# Wireless.net
KiCad netlist of a schematic drawn in EasyEDA
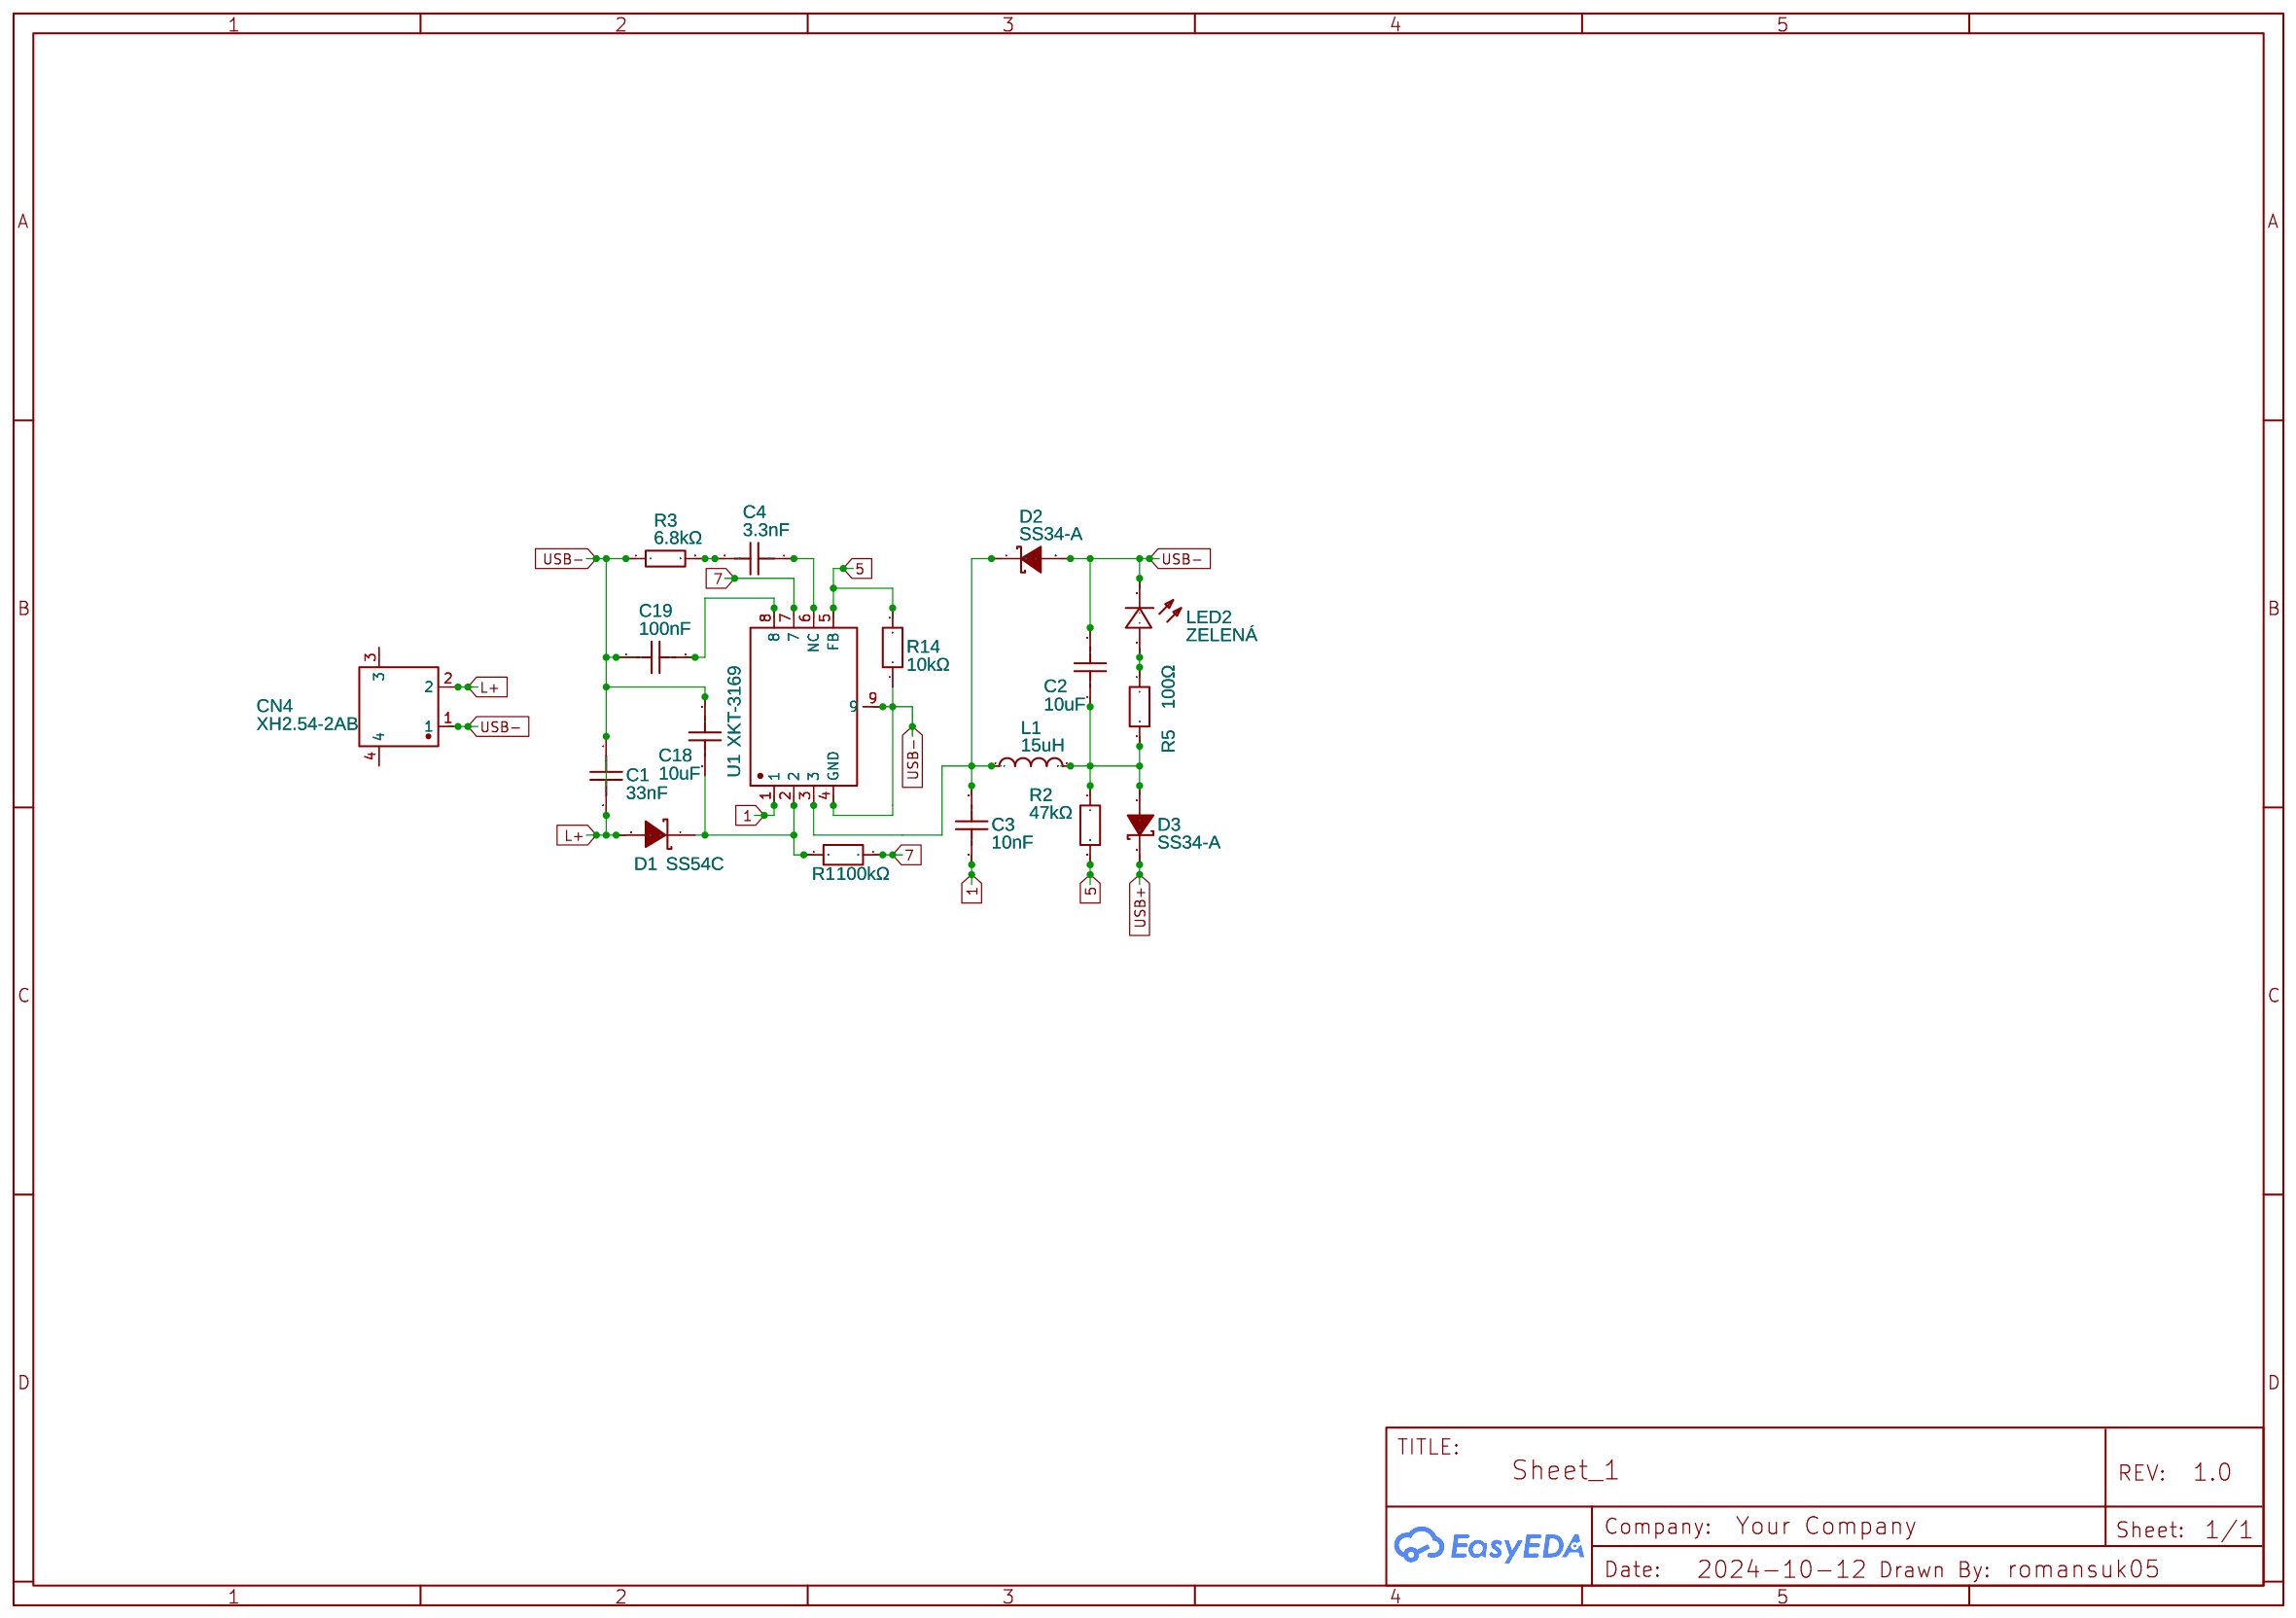
[diagram p0: schematic sheet]

(export (version "E")
  (design (tool "Eeschema 10.0.6"))
  (components
    (comp (ref "C1")
      (value "33nF")
      (fields
        (field (name "Manufacturer Part") "GRM31CR72E333KW03L")
        (field (name "Manufacturer") "muRata(村田)")
      )
      (libsource (lib "") (part "GRM31CR72E333KW03L"))
    )
    (comp (ref "C2")
      (value "10uF")
      (fields
        (field (name "Manufacturer Part") "TCC1206X7R106K250HT")
        (field (name "Manufacturer") "CCTC(三环)")
      )
      (libsource (lib "") (part "TCC1206X7R106K250HT"))
    )
    (comp (ref "C3")
      (value "10nF")
      (fields
        (field (name "Manufacturer Part") "CC1206JKNPOZBN103")
        (field (name "Manufacturer") "YAGEO(国巨)")
      )
      (libsource (lib "") (part "CC1206JKNPOZBN103"))
    )
    (comp (ref "C4")
      (value "3.3nF")
      (fields
        (field (name "Manufacturer Part") "TCC1206X7R332K501DT")
        (field (name "Manufacturer") "CCTC(三环)")
      )
      (libsource (lib "") (part "TCC1206X7R332K501DT"))
    )
    (comp (ref "C18")
      (value "10uF")
      (fields
        (field (name "Manufacturer Part") "TCC1206X7R106K250HT")
        (field (name "Manufacturer") "CCTC(三环)")
      )
      (libsource (lib "") (part "TCC1206X7R106K250HT"))
    )
    (comp (ref "C19")
      (value "100nF")
      (fields
        (field (name "Manufacturer Part") "C1206X104J1RECAUTO7210")
        (field (name "Manufacturer") "KEMET(基美)")
      )
      (libsource (lib "") (part "C1206X104J1RECAUTO7210"))
    )
    (comp (ref "CN4")
      (value "XH2.54-2AB")
      (fields (field (name "Manufacturer Part") "XH-2P立贴") (field (name "Manufacturer") "BOOMELE(博穆精密)"))
      (libsource (lib "") (part "XH2.54-2AB"))
    )
    (comp (ref "D1")
      (value "SS54C")
      (fields (field (name "Manufacturer Part") "SS54") (field (name "Manufacturer") "LGE(鲁光)"))
      (libsource (lib "") (part "SS54C"))
    )
    (comp (ref "D2")
      (value "SS34-A")
      (fields (field (name "Manufacturer") "FMS(美丽微)"))
      (libsource (lib "") (part "SS34-A"))
    )
    (comp (ref "D3")
      (value "SS34-A")
      (fields (field (name "Manufacturer") "FMS(美丽微)"))
      (libsource (lib "") (part "SS34-A_1"))
    )
    (comp (ref "L1")
      (value "15uH")
      (fields
        (field (name "Manufacturer Part") "MSCD43-150KT")
        (field (name "Manufacturer") "MetalLions(美铼)")
      )
      (libsource (lib "") (part "MSCD43-150KT"))
    )
    (comp (ref "LED2")
      (value "ZELENÁ")
      (fields
        (field (name "Manufacturer Part") "E6C1206URAC1UDA")
        (field (name "Manufacturer") "ekinglux(亿晶源)")
      )
      (libsource (lib "") (part "E6C1206URAC1UDA"))
    )
    (comp (ref "R1")
      (value "100kΩ")
      (fields (field (name "Manufacturer Part") "PTFR1206B100KN9") (field (name "Manufacturer") "RESI(开步睿思)"))
      (libsource (lib "") (part "PTFR1206B100KN9"))
    )
    (comp (ref "R2")
      (value "47kΩ")
      (fields
        (field (name "Manufacturer Part") "CR1206J47KP05")
        (field (name "Manufacturer") "EVER OHMS(天二科技)")
      )
      (libsource (lib "") (part "CR1206J47KP05"))
    )
    (comp (ref "R3")
      (value "6.8kΩ")
      (fields (field (name "Manufacturer Part") "AC1206FR-076K8L") (field (name "Manufacturer") "YAGEO(国巨)"))
      (libsource (lib "") (part "AC1206FR-076K8L"))
    )
    (comp (ref "R5")
      (value "100Ω")
      (fields (field (name "Manufacturer Part") "SCR1206F100R") (field (name "Manufacturer") "VO(翔胜)"))
      (libsource (lib "") (part "SCR1206F100R"))
    )
    (comp (ref "R14")
      (value "10kΩ")
      (fields (field (name "Manufacturer Part") "SCR1206F10K") (field (name "Manufacturer") "VO(翔胜)"))
      (libsource (lib "") (part "SCR1206F10K"))
    )
    (comp (ref "U1")
      (value "XKT-3169")
      (fields (field (name "Manufacturer") "MAXIM"))
      (libsource (lib "") (part "XKT-3169"))
    )
  )
  (nets
    (net (code "1") (name "1") (class "Default")
      (node (ref "C3") (pin "1") (pinfunction "1_1") (pintype "unspecified"))
      (node (ref "U1") (pin "1") (pinfunction "1_1") (pintype "unspecified"))
    )
    (net (code "2") (name "5") (class "Default")
      (node (ref "R14") (pin "2") (pinfunction "2_2") (pintype "unspecified"))
      (node (ref "R2") (pin "2") (pinfunction "2_2") (pintype "unspecified"))
      (node (ref "U1") (pin "5") (pinfunction "FB_5") (pintype "unspecified"))
    )
    (net (code "3") (name "7") (class "Default")
      (node (ref "R1") (pin "2") (pinfunction "2_2") (pintype "unspecified"))
      (node (ref "U1") (pin "7") (pinfunction "7_7") (pintype "unspecified"))
    )
    (net (code "4") (name "L+") (class "Default")
      (node (ref "C1") (pin "2") (pinfunction "2_2") (pintype "unspecified"))
      (node (ref "CN4") (pin "2") (pinfunction "2_2") (pintype "unspecified"))
      (node (ref "D1") (pin "2") (pinfunction "A_2") (pintype "unspecified"))
    )
    (net (code "5") (name "Net-(C4-Pad2)") (class "Default")
      (node (ref "C4") (pin "2") (pinfunction "2_2") (pintype "unspecified"))
      (node (ref "R3") (pin "2") (pinfunction "2_2") (pintype "unspecified"))
    )
    (net (code "6") (name "Net-(C19-Pad2)") (class "Default")
      (node (ref "C19") (pin "2") (pinfunction "2_2") (pintype "unspecified"))
      (node (ref "U1") (pin "8") (pinfunction "8_8") (pintype "unspecified"))
    )
    (net (code "7") (name "Net-(D1-K)") (class "Default")
      (node (ref "C18") (pin "2") (pinfunction "2_2") (pintype "unspecified"))
      (node (ref "D1") (pin "1") (pinfunction "K_1") (pintype "unspecified"))
      (node (ref "R1") (pin "1") (pinfunction "1_1") (pintype "unspecified"))
      (node (ref "U1") (pin "2") (pinfunction "2_2") (pintype "unspecified"))
    )
    (net (code "8") (name "Net-(D2-C)") (class "Default")
      (node (ref "C3") (pin "2") (pinfunction "2_2") (pintype "unspecified"))
      (node (ref "D2") (pin "1") (pinfunction "C_1") (pintype "unspecified"))
      (node (ref "L1") (pin "1") (pinfunction "1_1") (pintype "unspecified"))
      (node (ref "U1") (pin "3") (pinfunction "3_3") (pintype "unspecified"))
    )
    (net (code "9") (name "Net-(D3-A)") (class "Default")
      (node (ref "C2") (pin "2") (pinfunction "2_2") (pintype "unspecified"))
      (node (ref "D3") (pin "2") (pinfunction "A_2") (pintype "unspecified"))
      (node (ref "L1") (pin "2") (pinfunction "2_2") (pintype "unspecified"))
      (node (ref "R2") (pin "1") (pinfunction "1_1") (pintype "unspecified"))
      (node (ref "R5") (pin "2") (pinfunction "2_2") (pintype "unspecified"))
    )
    (net (code "10") (name "Net-(LED2-+)") (class "Default")
      (node (ref "LED2") (pin "1") (pinfunction "+_1") (pintype "unspecified"))
      (node (ref "R5") (pin "1") (pinfunction "1_1") (pintype "unspecified"))
    )
    (net (code "11") (name "Net-(U1-NC)") (class "Default")
      (node (ref "C4") (pin "1") (pinfunction "1_1") (pintype "unspecified"))
      (node (ref "U1") (pin "6") (pinfunction "NC_6") (pintype "unspecified"))
    )
    (net (code "12") (name "USB+") (class "Default")
      (node (ref "D3") (pin "1") (pinfunction "C_1") (pintype "unspecified"))
    )
    (net (code "13") (name "USB-") (class "Default")
      (node (ref "C1") (pin "1") (pinfunction "1_1") (pintype "unspecified"))
      (node (ref "C18") (pin "1") (pinfunction "1_1") (pintype "unspecified"))
      (node (ref "C19") (pin "1") (pinfunction "1_1") (pintype "unspecified"))
      (node (ref "C2") (pin "1") (pinfunction "1_1") (pintype "unspecified"))
      (node (ref "CN4") (pin "1") (pinfunction "1_1") (pintype "unspecified"))
      (node (ref "D2") (pin "2") (pinfunction "A_2") (pintype "unspecified"))
      (node (ref "LED2") (pin "2") (pinfunction "-_2") (pintype "unspecified"))
      (node (ref "R14") (pin "1") (pinfunction "1_1") (pintype "unspecified"))
      (node (ref "R3") (pin "1") (pinfunction "1_1") (pintype "unspecified"))
      (node (ref "U1") (pin "4") (pinfunction "GND_4") (pintype "unspecified"))
      (node (ref "U1") (pin "9") (pinfunction "9_9") (pintype "unspecified"))
    )
    (net (code "14") (name "unconnected-(CN4-Pad3)") (class "Default")
      (node (ref "CN4") (pin "3") (pinfunction "3_3") (pintype "unspecified"))
    )
    (net (code "15") (name "unconnected-(CN4-Pad4)") (class "Default")
      (node (ref "CN4") (pin "4") (pinfunction "4_4") (pintype "unspecified"))
    )
  )
)
